# C12666-vertical.net
KiCad netlist of a schematic drawn in EAGLE
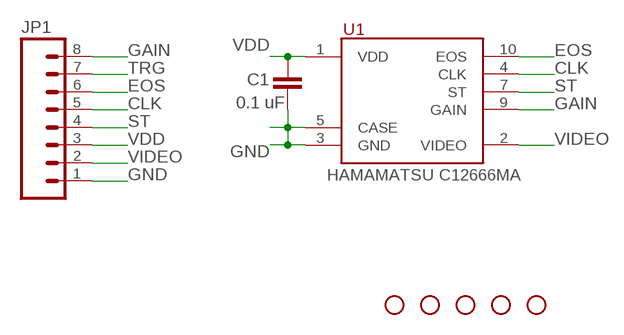
[diagram p0: schematic, sheet 1]

(export (version "E")
  (design (tool "Eeschema 10.0.6"))
  (components
    (comp (ref "C1")
      (value "0.1 uF")
      (footprint "eagle-import:C0805")
      (libsource (lib "eagle-import") (part "C-EUC0805"))
    )
    (comp (ref "JP1")
      (value "M08SILK_FEMALE_PTH")
      (footprint "eagle-import:1X08")
      (libsource (lib "eagle-import") (part "M08SILK_FEMALE_PTH"))
    )
    (comp (ref "STANDOFF1")
      (value "STAND-OFF")
      (footprint "eagle-import:STAND-OFF")
      (libsource (lib "eagle-import") (part "STAND-OFF"))
    )
    (comp (ref "STANDOFF2")
      (value "STAND-OFF")
      (footprint "eagle-import:STAND-OFF")
      (libsource (lib "eagle-import") (part "STAND-OFF"))
    )
    (comp (ref "STANDOFF3")
      (value "STAND-OFF")
      (footprint "eagle-import:STAND-OFF")
      (libsource (lib "eagle-import") (part "STAND-OFF"))
    )
    (comp (ref "STANDOFF4")
      (value "STAND-OFF")
      (footprint "eagle-import:STAND-OFF")
      (libsource (lib "eagle-import") (part "STAND-OFF"))
    )
    (comp (ref "STANDOFF5")
      (value "STAND-OFF")
      (footprint "eagle-import:STAND-OFF")
      (libsource (lib "eagle-import") (part "STAND-OFF"))
    )
    (comp (ref "U1")
      (value "MICROSPEC-C12666MA")
      (footprint "eagle-import:C12666MA")
      (libsource (lib "eagle-import") (part "MICROSPEC-C12666MA"))
    )
  )
  (nets
    (net (code "1") (name "/CLK") (class "Default")
      (node (ref "JP1") (pin "5") (pinfunction "5_5") (pintype "passive"))
      (node (ref "U1") (pin "4") (pinfunction "CLK_4") (pintype "bidirectional"))
    )
    (net (code "2") (name "/EOS") (class "Default")
      (node (ref "JP1") (pin "6") (pinfunction "6_6") (pintype "passive"))
      (node (ref "U1") (pin "10") (pinfunction "EOS_10") (pintype "bidirectional"))
    )
    (net (code "3") (name "/GAIN") (class "Default")
      (node (ref "JP1") (pin "8") (pinfunction "8_8") (pintype "passive"))
      (node (ref "U1") (pin "9") (pinfunction "GAIN_9") (pintype "bidirectional"))
    )
    (net (code "4") (name "/GND") (class "Default")
      (node (ref "C1") (pin "2") (pinfunction "2_2") (pintype "passive"))
      (node (ref "JP1") (pin "1") (pinfunction "1_1") (pintype "passive"))
      (node (ref "U1") (pin "3") (pinfunction "GND_3") (pintype "bidirectional"))
      (node (ref "U1") (pin "5") (pinfunction "CASE_5") (pintype "bidirectional"))
    )
    (net (code "5") (name "/ST") (class "Default")
      (node (ref "JP1") (pin "4") (pinfunction "4_4") (pintype "passive"))
      (node (ref "U1") (pin "7") (pinfunction "ST_7") (pintype "bidirectional"))
    )
    (net (code "6") (name "/TRG") (class "Default")
      (node (ref "JP1") (pin "7") (pinfunction "7_7") (pintype "passive"))
    )
    (net (code "7") (name "/VDD") (class "Default")
      (node (ref "C1") (pin "1") (pinfunction "1_1") (pintype "passive"))
      (node (ref "JP1") (pin "3") (pinfunction "3_3") (pintype "passive"))
      (node (ref "U1") (pin "1") (pinfunction "VDD_1") (pintype "bidirectional"))
    )
    (net (code "8") (name "/VIDEO") (class "Default")
      (node (ref "JP1") (pin "2") (pinfunction "2_2") (pintype "passive"))
      (node (ref "U1") (pin "2") (pinfunction "VIDEO_2") (pintype "bidirectional"))
    )
  )
)
